# LED_Cube_V6.net
KiCad netlist of a schematic drawn in EAGLE
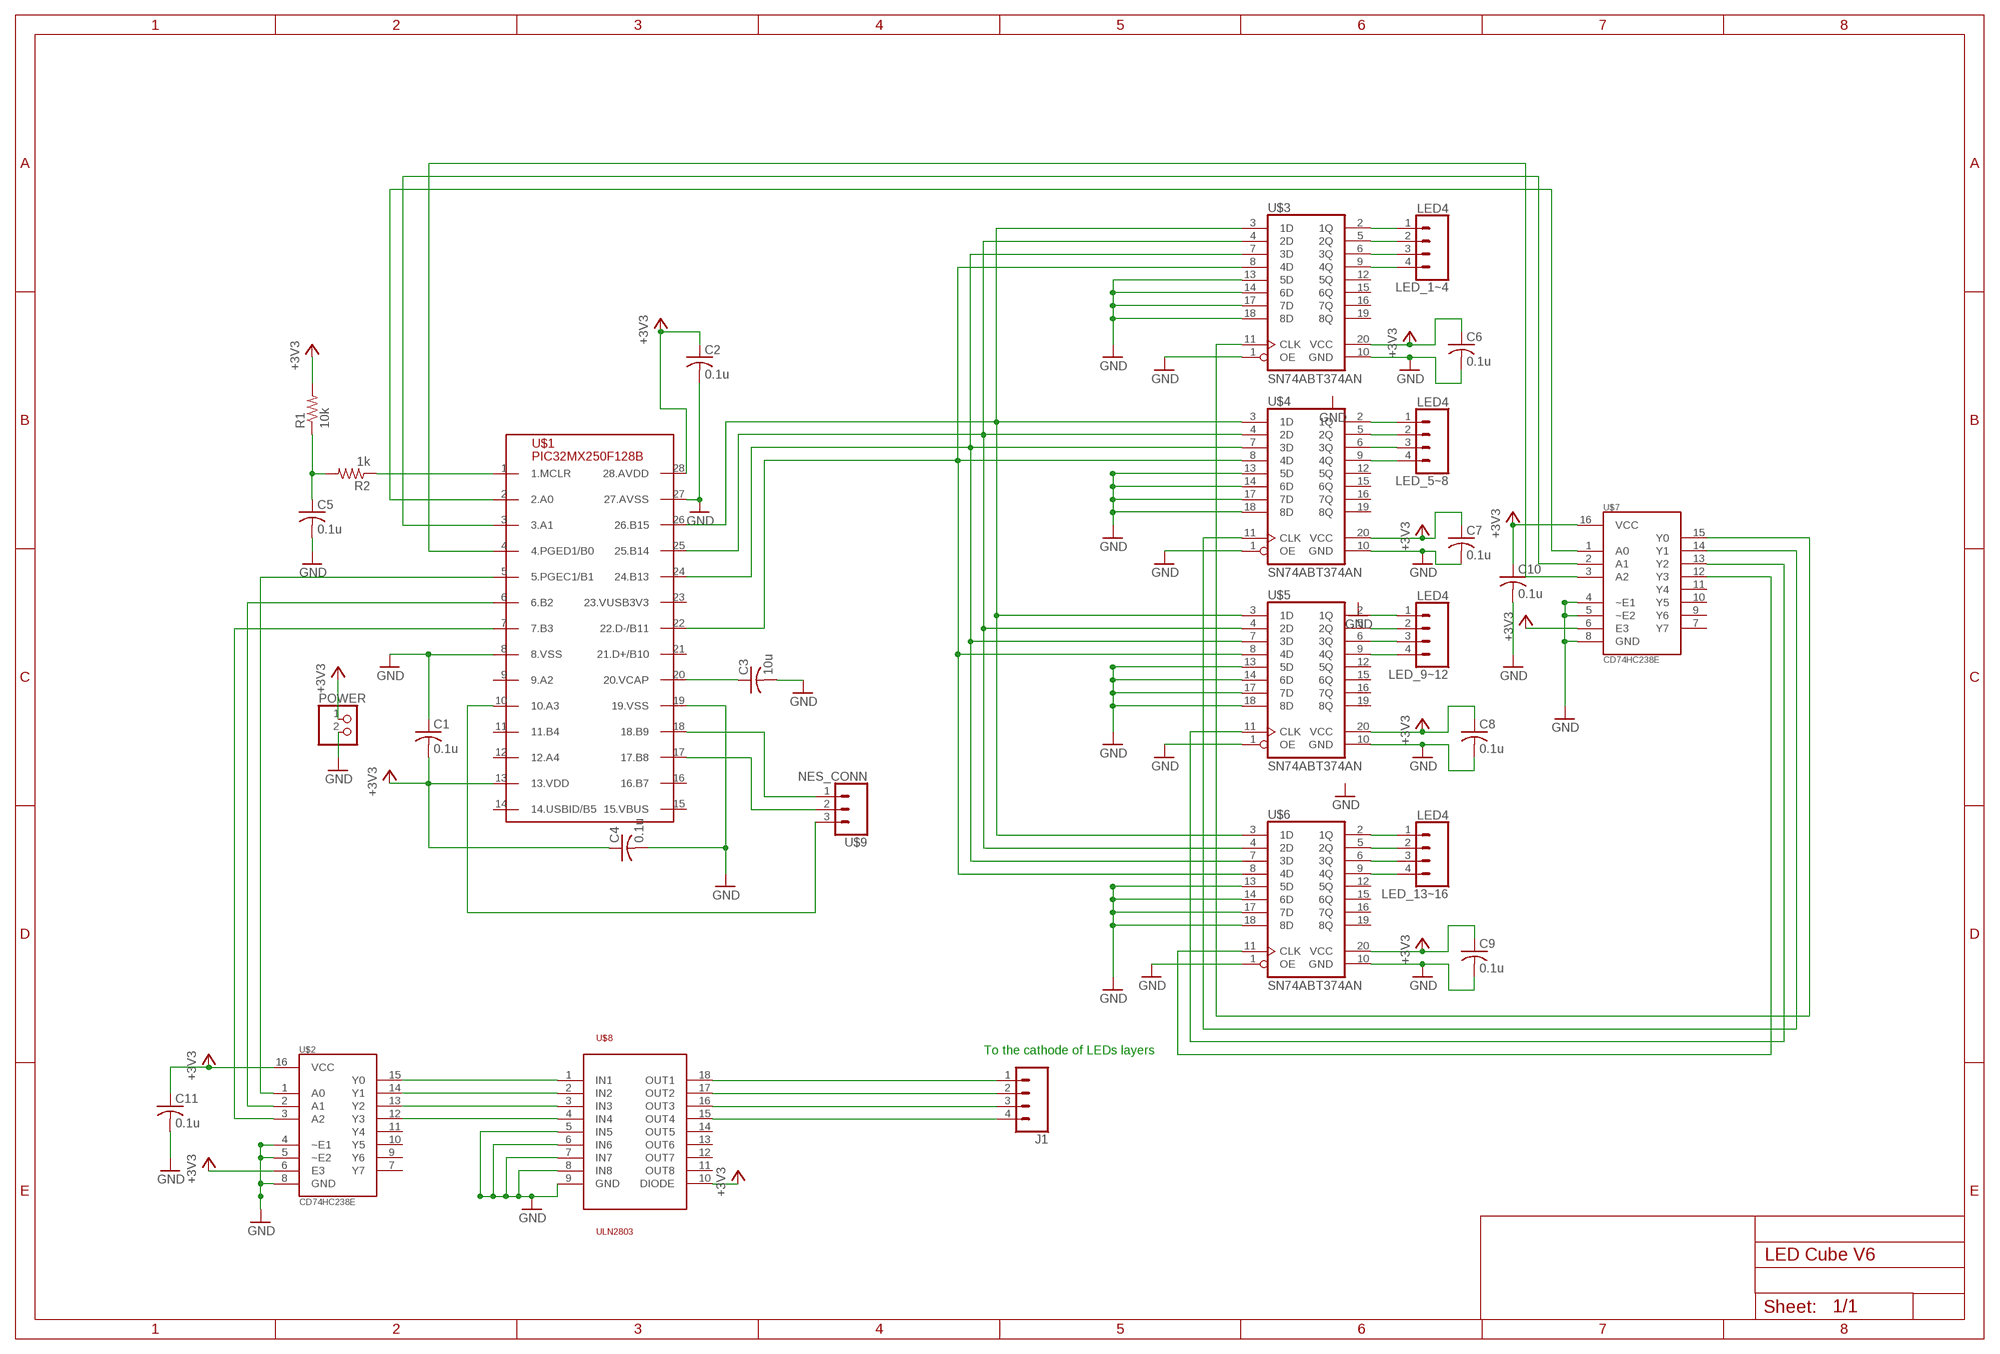
[diagram p0: schematic, sheet 1]

(export (version "E")
  (design (tool "Eeschema 10.0.6"))
  (components
    (comp (ref "C1")
      (value "0.1u")
      (footprint "eagle-import:C025-025X050")
      (libsource (lib "eagle-import") (part "C-US025-025X050"))
    )
    (comp (ref "C2")
      (value "0.1u")
      (footprint "eagle-import:C025-025X050")
      (libsource (lib "eagle-import") (part "C-US025-025X050"))
    )
    (comp (ref "C3")
      (value "10u")
      (footprint "eagle-import:C025-025X050")
      (libsource (lib "eagle-import") (part "C-US025-025X050"))
    )
    (comp (ref "C4")
      (value "0.1u")
      (footprint "eagle-import:C025-025X050")
      (libsource (lib "eagle-import") (part "C-US025-025X050"))
    )
    (comp (ref "C5")
      (value "0.1u")
      (footprint "eagle-import:C025-025X050")
      (libsource (lib "eagle-import") (part "C-US025-025X050"))
    )
    (comp (ref "C6")
      (value "0.1u")
      (footprint "eagle-import:C025-025X050")
      (libsource (lib "eagle-import") (part "C-US025-025X050"))
    )
    (comp (ref "C7")
      (value "0.1u")
      (footprint "eagle-import:C025-025X050")
      (libsource (lib "eagle-import") (part "C-US025-025X050"))
    )
    (comp (ref "C8")
      (value "0.1u")
      (footprint "eagle-import:C025-025X050")
      (libsource (lib "eagle-import") (part "C-US025-025X050"))
    )
    (comp (ref "C9")
      (value "0.1u")
      (footprint "eagle-import:C025-025X050")
      (libsource (lib "eagle-import") (part "C-US025-025X050"))
    )
    (comp (ref "C10")
      (value "0.1u")
      (footprint "eagle-import:C025-025X050")
      (libsource (lib "eagle-import") (part "C-US025-025X050"))
    )
    (comp (ref "C11")
      (value "0.1u")
      (footprint "eagle-import:C025-025X050")
      (libsource (lib "eagle-import") (part "C-US025-025X050"))
    )
    (comp (ref "J1")
      (value "CONN_04")
      (footprint "eagle-import:1X04")
      (libsource (lib "eagle-import") (part "CONN_04"))
    )
    (comp (ref "LED_1~4")
      (value "LED4")
      (footprint "eagle-import:1X04")
      (libsource (lib "eagle-import") (part "LED4"))
    )
    (comp (ref "LED_5~8")
      (value "LED4")
      (footprint "eagle-import:1X04")
      (libsource (lib "eagle-import") (part "LED4"))
    )
    (comp (ref "LED_9~12")
      (value "LED4")
      (footprint "eagle-import:1X04")
      (libsource (lib "eagle-import") (part "LED4"))
    )
    (comp (ref "LED_13~16")
      (value "LED4")
      (footprint "eagle-import:1X04")
      (libsource (lib "eagle-import") (part "LED4"))
    )
    (comp (ref "POWER")
      (value "PINHD-1X2")
      (footprint "eagle-import:1X02")
      (libsource (lib "eagle-import") (part "PINHD-1X2"))
    )
    (comp (ref "R1")
      (value "10k")
      (footprint "eagle-import:0204_7")
      (libsource (lib "eagle-import") (part "R-US_0204/7"))
    )
    (comp (ref "R2")
      (value "1k")
      (footprint "eagle-import:0204_7")
      (libsource (lib "eagle-import") (part "R-US_0204/7"))
    )
    (comp (ref "U$1")
      (value "PIC32MX250F128B")
      (footprint "eagle-import:DIL28-3")
      (libsource (lib "eagle-import") (part "PIC32MX250F128B"))
    )
    (comp (ref "U$2")
      (value "CD74HC238E")
      (footprint "eagle-import:DIL16")
      (libsource (lib "eagle-import") (part "CD74HC238E"))
    )
    (comp (ref "U$3")
      (value "SN74ABT374AN")
      (footprint "eagle-import:DIL20")
      (libsource (lib "eagle-import") (part "SN74ABT374AN"))
    )
    (comp (ref "U$4")
      (value "SN74ABT374AN")
      (footprint "eagle-import:DIL20")
      (libsource (lib "eagle-import") (part "SN74ABT374AN"))
    )
    (comp (ref "U$5")
      (value "SN74ABT374AN")
      (footprint "eagle-import:DIL20")
      (libsource (lib "eagle-import") (part "SN74ABT374AN"))
    )
    (comp (ref "U$6")
      (value "SN74ABT374AN")
      (footprint "eagle-import:DIL20")
      (libsource (lib "eagle-import") (part "SN74ABT374AN"))
    )
    (comp (ref "U$7")
      (value "CD74HC238E")
      (footprint "eagle-import:DIL16")
      (libsource (lib "eagle-import") (part "CD74HC238E"))
    )
    (comp (ref "U$8")
      (value "ULN2803")
      (footprint "eagle-import:SO18L")
      (libsource (lib "eagle-import") (part "ULN2803"))
    )
    (comp (ref "U$9")
      (value "NES_CONN")
      (footprint "eagle-import:1X03")
      (libsource (lib "eagle-import") (part "NES_CONN"))
    )
  )
  (nets
    (net (code "1") (name "+3V3") (class "Default")
      (node (ref "C1") (pin "2") (pinfunction "2_2") (pintype "passive"))
      (node (ref "C10") (pin "1") (pinfunction "1_1") (pintype "passive"))
      (node (ref "C11") (pin "1") (pinfunction "1_1") (pintype "passive"))
      (node (ref "C2") (pin "1") (pinfunction "1_1") (pintype "passive"))
      (node (ref "C4") (pin "1") (pinfunction "1_1") (pintype "passive"))
      (node (ref "C6") (pin "1") (pinfunction "1_1") (pintype "passive"))
      (node (ref "C7") (pin "1") (pinfunction "1_1") (pintype "passive"))
      (node (ref "C8") (pin "1") (pinfunction "1_1") (pintype "passive"))
      (node (ref "C9") (pin "1") (pinfunction "1_1") (pintype "passive"))
      (node (ref "POWER") (pin "1") (pinfunction "1_1") (pintype "passive"))
      (node (ref "R1") (pin "2") (pinfunction "2_2") (pintype "passive"))
      (node (ref "U$1") (pin "13") (pinfunction "13.VDD_13") (pintype "bidirectional"))
      (node (ref "U$1") (pin "28") (pinfunction "28.AVDD_28") (pintype "bidirectional"))
      (node (ref "U$2") (pin "16") (pinfunction "VCC_16") (pintype "bidirectional"))
      (node (ref "U$2") (pin "6") (pinfunction "E3_6") (pintype "bidirectional"))
      (node (ref "U$3") (pin "20") (pinfunction "VCC_20") (pintype "bidirectional"))
      (node (ref "U$4") (pin "20") (pinfunction "VCC_20") (pintype "bidirectional"))
      (node (ref "U$5") (pin "20") (pinfunction "VCC_20") (pintype "bidirectional"))
      (node (ref "U$6") (pin "20") (pinfunction "VCC_20") (pintype "bidirectional"))
      (node (ref "U$7") (pin "16") (pinfunction "VCC_16") (pintype "bidirectional"))
      (node (ref "U$7") (pin "6") (pinfunction "E3_6") (pintype "bidirectional"))
      (node (ref "U$8") (pin "10") (pinfunction "DIODE_10") (pintype "power_in"))
    )
    (net (code "2") (name "GND") (class "Default")
      (node (ref "C1") (pin "1") (pinfunction "1_1") (pintype "passive"))
      (node (ref "C10") (pin "2") (pinfunction "2_2") (pintype "passive"))
      (node (ref "C11") (pin "2") (pinfunction "2_2") (pintype "passive"))
      (node (ref "C2") (pin "2") (pinfunction "2_2") (pintype "passive"))
      (node (ref "C3") (pin "2") (pinfunction "2_2") (pintype "passive"))
      (node (ref "C4") (pin "2") (pinfunction "2_2") (pintype "passive"))
      (node (ref "C5") (pin "2") (pinfunction "2_2") (pintype "passive"))
      (node (ref "C6") (pin "2") (pinfunction "2_2") (pintype "passive"))
      (node (ref "C7") (pin "2") (pinfunction "2_2") (pintype "passive"))
      (node (ref "C8") (pin "2") (pinfunction "2_2") (pintype "passive"))
      (node (ref "C9") (pin "2") (pinfunction "2_2") (pintype "passive"))
      (node (ref "POWER") (pin "2") (pinfunction "2_2") (pintype "passive"))
      (node (ref "U$1") (pin "19") (pinfunction "19.VSS_19") (pintype "bidirectional"))
      (node (ref "U$1") (pin "27") (pinfunction "27.AVSS_27") (pintype "bidirectional"))
      (node (ref "U$1") (pin "8") (pinfunction "8.VSS_8") (pintype "bidirectional"))
      (node (ref "U$2") (pin "4") (pinfunction "~{E1}_4") (pintype "bidirectional"))
      (node (ref "U$2") (pin "5") (pinfunction "~{E2}_5") (pintype "bidirectional"))
      (node (ref "U$2") (pin "8") (pinfunction "GND_8") (pintype "bidirectional"))
      (node (ref "U$3") (pin "1") (pinfunction "OE_1") (pintype "input"))
      (node (ref "U$3") (pin "10") (pinfunction "GND_10") (pintype "bidirectional"))
      (node (ref "U$3") (pin "13") (pinfunction "5D_13") (pintype "input"))
      (node (ref "U$3") (pin "14") (pinfunction "6D_14") (pintype "input"))
      (node (ref "U$3") (pin "17") (pinfunction "7D_17") (pintype "input"))
      (node (ref "U$3") (pin "18") (pinfunction "8D_18") (pintype "input"))
      (node (ref "U$4") (pin "1") (pinfunction "OE_1") (pintype "input"))
      (node (ref "U$4") (pin "10") (pinfunction "GND_10") (pintype "bidirectional"))
      (node (ref "U$4") (pin "13") (pinfunction "5D_13") (pintype "input"))
      (node (ref "U$4") (pin "14") (pinfunction "6D_14") (pintype "input"))
      (node (ref "U$4") (pin "17") (pinfunction "7D_17") (pintype "input"))
      (node (ref "U$4") (pin "18") (pinfunction "8D_18") (pintype "input"))
      (node (ref "U$5") (pin "1") (pinfunction "OE_1") (pintype "input"))
      (node (ref "U$5") (pin "10") (pinfunction "GND_10") (pintype "bidirectional"))
      (node (ref "U$5") (pin "13") (pinfunction "5D_13") (pintype "input"))
      (node (ref "U$5") (pin "14") (pinfunction "6D_14") (pintype "input"))
      (node (ref "U$5") (pin "17") (pinfunction "7D_17") (pintype "input"))
      (node (ref "U$5") (pin "18") (pinfunction "8D_18") (pintype "input"))
      (node (ref "U$6") (pin "1") (pinfunction "OE_1") (pintype "input"))
      (node (ref "U$6") (pin "10") (pinfunction "GND_10") (pintype "bidirectional"))
      (node (ref "U$6") (pin "13") (pinfunction "5D_13") (pintype "input"))
      (node (ref "U$6") (pin "14") (pinfunction "6D_14") (pintype "input"))
      (node (ref "U$6") (pin "17") (pinfunction "7D_17") (pintype "input"))
      (node (ref "U$6") (pin "18") (pinfunction "8D_18") (pintype "input"))
      (node (ref "U$7") (pin "4") (pinfunction "~{E1}_4") (pintype "bidirectional"))
      (node (ref "U$7") (pin "5") (pinfunction "~{E2}_5") (pintype "bidirectional"))
      (node (ref "U$7") (pin "8") (pinfunction "GND_8") (pintype "bidirectional"))
      (node (ref "U$8") (pin "5") (pinfunction "IN5_5") (pintype "input"))
      (node (ref "U$8") (pin "6") (pinfunction "IN6_6") (pintype "input"))
      (node (ref "U$8") (pin "7") (pinfunction "IN7_7") (pintype "input"))
      (node (ref "U$8") (pin "8") (pinfunction "IN8_8") (pintype "input"))
      (node (ref "U$8") (pin "9") (pinfunction "GND_9") (pintype "power_in"))
    )
    (net (code "3") (name "Net-(C5-Pad1)") (class "Default")
      (node (ref "C5") (pin "1") (pinfunction "1_1") (pintype "passive"))
      (node (ref "R1") (pin "1") (pinfunction "1_1") (pintype "passive"))
      (node (ref "R2") (pin "2") (pinfunction "2_2") (pintype "passive"))
    )
    (net (code "4") (name "Net-(U$1-1.MCLR)") (class "Default")
      (node (ref "R2") (pin "1") (pinfunction "1_1") (pintype "passive"))
      (node (ref "U$1") (pin "1") (pinfunction "1.MCLR_1") (pintype "bidirectional"))
    )
    (net (code "5") (name "Net-(U$1-2.A0)") (class "Default")
      (node (ref "U$1") (pin "2") (pinfunction "2.A0_2") (pintype "bidirectional"))
      (node (ref "U$7") (pin "1") (pinfunction "A0_1") (pintype "bidirectional"))
    )
    (net (code "6") (name "Net-(U$1-3.A1)") (class "Default")
      (node (ref "U$1") (pin "3") (pinfunction "3.A1_3") (pintype "bidirectional"))
      (node (ref "U$7") (pin "2") (pinfunction "A1_2") (pintype "bidirectional"))
    )
    (net (code "7") (name "Net-(U$1-4.PGED1{slash}B0)") (class "Default")
      (node (ref "U$1") (pin "4") (pinfunction "4.PGED1/B0_4") (pintype "bidirectional"))
      (node (ref "U$7") (pin "3") (pinfunction "A2_3") (pintype "bidirectional"))
    )
    (net (code "8") (name "Net-(U$1-5.PGEC1{slash}B1)") (class "Default")
      (node (ref "U$1") (pin "5") (pinfunction "5.PGEC1/B1_5") (pintype "bidirectional"))
      (node (ref "U$2") (pin "1") (pinfunction "A0_1") (pintype "bidirectional"))
    )
    (net (code "9") (name "Net-(U$1-6.B2)") (class "Default")
      (node (ref "U$1") (pin "6") (pinfunction "6.B2_6") (pintype "bidirectional"))
      (node (ref "U$2") (pin "2") (pinfunction "A1_2") (pintype "bidirectional"))
    )
    (net (code "10") (name "Net-(U$1-7.B3)") (class "Default")
      (node (ref "U$1") (pin "7") (pinfunction "7.B3_7") (pintype "bidirectional"))
      (node (ref "U$2") (pin "3") (pinfunction "A2_3") (pintype "bidirectional"))
    )
    (net (code "11") (name "Net-(U$1-10.A3)") (class "Default")
      (node (ref "U$1") (pin "10") (pinfunction "10.A3_10") (pintype "bidirectional"))
      (node (ref "U$9") (pin "3") (pinfunction "3_3") (pintype "passive"))
    )
    (net (code "12") (name "Net-(U$1-17.B8)") (class "Default")
      (node (ref "U$1") (pin "17") (pinfunction "17.B8_17") (pintype "bidirectional"))
      (node (ref "U$9") (pin "2") (pinfunction "2_2") (pintype "passive"))
    )
    (net (code "13") (name "Net-(U$1-18.B9)") (class "Default")
      (node (ref "U$1") (pin "18") (pinfunction "18.B9_18") (pintype "bidirectional"))
      (node (ref "U$9") (pin "1") (pinfunction "1_1") (pintype "passive"))
    )
    (net (code "14") (name "Net-(U$1-20.VCAP)") (class "Default")
      (node (ref "C3") (pin "1") (pinfunction "1_1") (pintype "passive"))
      (node (ref "U$1") (pin "20") (pinfunction "20.VCAP_20") (pintype "bidirectional"))
    )
    (net (code "15") (name "Net-(U$1-22.D-{slash}B11)") (class "Default")
      (node (ref "U$1") (pin "22") (pinfunction "22.D-/B11_22") (pintype "bidirectional"))
      (node (ref "U$3") (pin "8") (pinfunction "4D_8") (pintype "input"))
      (node (ref "U$4") (pin "8") (pinfunction "4D_8") (pintype "input"))
      (node (ref "U$5") (pin "8") (pinfunction "4D_8") (pintype "input"))
      (node (ref "U$6") (pin "8") (pinfunction "4D_8") (pintype "input"))
    )
    (net (code "16") (name "Net-(U$1-24.B13)") (class "Default")
      (node (ref "U$1") (pin "24") (pinfunction "24.B13_24") (pintype "bidirectional"))
      (node (ref "U$3") (pin "7") (pinfunction "3D_7") (pintype "input"))
      (node (ref "U$4") (pin "7") (pinfunction "3D_7") (pintype "input"))
      (node (ref "U$5") (pin "7") (pinfunction "3D_7") (pintype "input"))
      (node (ref "U$6") (pin "7") (pinfunction "3D_7") (pintype "input"))
    )
    (net (code "17") (name "Net-(U$1-25.B14)") (class "Default")
      (node (ref "U$1") (pin "25") (pinfunction "25.B14_25") (pintype "bidirectional"))
      (node (ref "U$3") (pin "4") (pinfunction "2D_4") (pintype "input"))
      (node (ref "U$4") (pin "4") (pinfunction "2D_4") (pintype "input"))
      (node (ref "U$5") (pin "4") (pinfunction "2D_4") (pintype "input"))
      (node (ref "U$6") (pin "4") (pinfunction "2D_4") (pintype "input"))
    )
    (net (code "18") (name "Net-(U$1-26.B15)") (class "Default")
      (node (ref "U$1") (pin "26") (pinfunction "26.B15_26") (pintype "bidirectional"))
      (node (ref "U$3") (pin "3") (pinfunction "1D_3") (pintype "input"))
      (node (ref "U$4") (pin "3") (pinfunction "1D_3") (pintype "input"))
      (node (ref "U$5") (pin "3") (pinfunction "1D_3") (pintype "input"))
      (node (ref "U$6") (pin "3") (pinfunction "1D_3") (pintype "input"))
    )
    (net (code "19") (name "Net-(U$2-Y0)") (class "Default")
      (node (ref "U$2") (pin "15") (pinfunction "Y0_15") (pintype "bidirectional"))
      (node (ref "U$8") (pin "1") (pinfunction "IN1_1") (pintype "input"))
    )
    (net (code "20") (name "Net-(U$2-Y1)") (class "Default")
      (node (ref "U$2") (pin "14") (pinfunction "Y1_14") (pintype "bidirectional"))
      (node (ref "U$8") (pin "2") (pinfunction "IN2_2") (pintype "input"))
    )
    (net (code "21") (name "Net-(U$2-Y2)") (class "Default")
      (node (ref "U$2") (pin "13") (pinfunction "Y2_13") (pintype "bidirectional"))
      (node (ref "U$8") (pin "3") (pinfunction "IN3_3") (pintype "input"))
    )
    (net (code "22") (name "Net-(U$2-Y3)") (class "Default")
      (node (ref "U$2") (pin "12") (pinfunction "Y3_12") (pintype "bidirectional"))
      (node (ref "U$8") (pin "4") (pinfunction "IN4_4") (pintype "input"))
    )
    (net (code "23") (name "Net-(U$3-1Q)") (class "Default")
      (node (ref "LED_1~4") (pin "1") (pinfunction "1_1") (pintype "passive"))
      (node (ref "U$3") (pin "2") (pinfunction "1Q_2") (pintype "tri_state"))
    )
    (net (code "24") (name "Net-(U$3-2Q)") (class "Default")
      (node (ref "LED_1~4") (pin "2") (pinfunction "2_2") (pintype "passive"))
      (node (ref "U$3") (pin "5") (pinfunction "2Q_5") (pintype "tri_state"))
    )
    (net (code "25") (name "Net-(U$3-3Q)") (class "Default")
      (node (ref "LED_1~4") (pin "3") (pinfunction "3_3") (pintype "passive"))
      (node (ref "U$3") (pin "6") (pinfunction "3Q_6") (pintype "tri_state"))
    )
    (net (code "26") (name "Net-(U$3-4Q)") (class "Default")
      (node (ref "LED_1~4") (pin "4") (pinfunction "4_4") (pintype "passive"))
      (node (ref "U$3") (pin "9") (pinfunction "4Q_9") (pintype "tri_state"))
    )
    (net (code "27") (name "Net-(U$3-CLK)") (class "Default")
      (node (ref "U$3") (pin "11") (pinfunction "CLK_11") (pintype "input"))
      (node (ref "U$7") (pin "15") (pinfunction "Y0_15") (pintype "bidirectional"))
    )
    (net (code "28") (name "Net-(U$4-1Q)") (class "Default")
      (node (ref "LED_5~8") (pin "1") (pinfunction "1_1") (pintype "passive"))
      (node (ref "U$4") (pin "2") (pinfunction "1Q_2") (pintype "tri_state"))
    )
    (net (code "29") (name "Net-(U$4-2Q)") (class "Default")
      (node (ref "LED_5~8") (pin "2") (pinfunction "2_2") (pintype "passive"))
      (node (ref "U$4") (pin "5") (pinfunction "2Q_5") (pintype "tri_state"))
    )
    (net (code "30") (name "Net-(U$4-3Q)") (class "Default")
      (node (ref "LED_5~8") (pin "3") (pinfunction "3_3") (pintype "passive"))
      (node (ref "U$4") (pin "6") (pinfunction "3Q_6") (pintype "tri_state"))
    )
    (net (code "31") (name "Net-(U$4-4Q)") (class "Default")
      (node (ref "LED_5~8") (pin "4") (pinfunction "4_4") (pintype "passive"))
      (node (ref "U$4") (pin "9") (pinfunction "4Q_9") (pintype "tri_state"))
    )
    (net (code "32") (name "Net-(U$4-CLK)") (class "Default")
      (node (ref "U$4") (pin "11") (pinfunction "CLK_11") (pintype "input"))
      (node (ref "U$7") (pin "14") (pinfunction "Y1_14") (pintype "bidirectional"))
    )
    (net (code "33") (name "Net-(U$5-1Q)") (class "Default")
      (node (ref "LED_9~12") (pin "1") (pinfunction "1_1") (pintype "passive"))
      (node (ref "U$5") (pin "2") (pinfunction "1Q_2") (pintype "tri_state"))
    )
    (net (code "34") (name "Net-(U$5-2Q)") (class "Default")
      (node (ref "LED_9~12") (pin "2") (pinfunction "2_2") (pintype "passive"))
      (node (ref "U$5") (pin "5") (pinfunction "2Q_5") (pintype "tri_state"))
    )
    (net (code "35") (name "Net-(U$5-3Q)") (class "Default")
      (node (ref "LED_9~12") (pin "3") (pinfunction "3_3") (pintype "passive"))
      (node (ref "U$5") (pin "6") (pinfunction "3Q_6") (pintype "tri_state"))
    )
    (net (code "36") (name "Net-(U$5-4Q)") (class "Default")
      (node (ref "LED_9~12") (pin "4") (pinfunction "4_4") (pintype "passive"))
      (node (ref "U$5") (pin "9") (pinfunction "4Q_9") (pintype "tri_state"))
    )
    (net (code "37") (name "Net-(U$5-CLK)") (class "Default")
      (node (ref "U$5") (pin "11") (pinfunction "CLK_11") (pintype "input"))
      (node (ref "U$7") (pin "13") (pinfunction "Y2_13") (pintype "bidirectional"))
    )
    (net (code "38") (name "Net-(U$6-1Q)") (class "Default")
      (node (ref "LED_13~16") (pin "1") (pinfunction "1_1") (pintype "passive"))
      (node (ref "U$6") (pin "2") (pinfunction "1Q_2") (pintype "tri_state"))
    )
    (net (code "39") (name "Net-(U$6-2Q)") (class "Default")
      (node (ref "LED_13~16") (pin "2") (pinfunction "2_2") (pintype "passive"))
      (node (ref "U$6") (pin "5") (pinfunction "2Q_5") (pintype "tri_state"))
    )
    (net (code "40") (name "Net-(U$6-3Q)") (class "Default")
      (node (ref "LED_13~16") (pin "3") (pinfunction "3_3") (pintype "passive"))
      (node (ref "U$6") (pin "6") (pinfunction "3Q_6") (pintype "tri_state"))
    )
    (net (code "41") (name "Net-(U$6-4Q)") (class "Default")
      (node (ref "LED_13~16") (pin "4") (pinfunction "4_4") (pintype "passive"))
      (node (ref "U$6") (pin "9") (pinfunction "4Q_9") (pintype "tri_state"))
    )
    (net (code "42") (name "Net-(U$6-CLK)") (class "Default")
      (node (ref "U$6") (pin "11") (pinfunction "CLK_11") (pintype "input"))
      (node (ref "U$7") (pin "12") (pinfunction "Y3_12") (pintype "bidirectional"))
    )
    (net (code "43") (name "Net-(U$8-OUT1)") (class "Default")
      (node (ref "J1") (pin "1") (pinfunction "1_1") (pintype "passive"))
      (node (ref "U$8") (pin "18") (pinfunction "OUT1_18") (pintype "open_collector"))
    )
    (net (code "44") (name "Net-(U$8-OUT2)") (class "Default")
      (node (ref "J1") (pin "2") (pinfunction "2_2") (pintype "passive"))
      (node (ref "U$8") (pin "17") (pinfunction "OUT2_17") (pintype "open_collector"))
    )
    (net (code "45") (name "Net-(U$8-OUT3)") (class "Default")
      (node (ref "J1") (pin "3") (pinfunction "3_3") (pintype "passive"))
      (node (ref "U$8") (pin "16") (pinfunction "OUT3_16") (pintype "open_collector"))
    )
    (net (code "46") (name "Net-(U$8-OUT4)") (class "Default")
      (node (ref "J1") (pin "4") (pinfunction "4_4") (pintype "passive"))
      (node (ref "U$8") (pin "15") (pinfunction "OUT4_15") (pintype "open_collector"))
    )
    (net (code "47") (name "unconnected-(U$1-9.A2-Pad9)") (class "Default")
      (node (ref "U$1") (pin "9") (pinfunction "9.A2_9") (pintype "bidirectional"))
    )
    (net (code "48") (name "unconnected-(U$1-11.B4-Pad11)") (class "Default")
      (node (ref "U$1") (pin "11") (pinfunction "11.B4_11") (pintype "bidirectional"))
    )
    (net (code "49") (name "unconnected-(U$1-12.A4-Pad12)") (class "Default")
      (node (ref "U$1") (pin "12") (pinfunction "12.A4_12") (pintype "bidirectional"))
    )
    (net (code "50") (name "unconnected-(U$1-14.USBID{slash}B5-Pad14)") (class "Default")
      (node (ref "U$1") (pin "14") (pinfunction "14.USBID/B5_14") (pintype "bidirectional"))
    )
    (net (code "51") (name "unconnected-(U$1-15.VBUS-Pad15)") (class "Default")
      (node (ref "U$1") (pin "15") (pinfunction "15.VBUS_15") (pintype "bidirectional"))
    )
    (net (code "52") (name "unconnected-(U$1-16.B7-Pad16)") (class "Default")
      (node (ref "U$1") (pin "16") (pinfunction "16.B7_16") (pintype "bidirectional"))
    )
    (net (code "53") (name "unconnected-(U$1-21.D+{slash}B10-Pad21)") (class "Default")
      (node (ref "U$1") (pin "21") (pinfunction "21.D+/B10_21") (pintype "bidirectional"))
    )
    (net (code "54") (name "unconnected-(U$1-23.VUSB3V3-Pad23)") (class "Default")
      (node (ref "U$1") (pin "23") (pinfunction "23.VUSB3V3_23") (pintype "bidirectional"))
    )
    (net (code "55") (name "unconnected-(U$2-Y4-Pad11)") (class "Default")
      (node (ref "U$2") (pin "11") (pinfunction "Y4_11") (pintype "bidirectional"))
    )
    (net (code "56") (name "unconnected-(U$2-Y5-Pad10)") (class "Default")
      (node (ref "U$2") (pin "10") (pinfunction "Y5_10") (pintype "bidirectional"))
    )
    (net (code "57") (name "unconnected-(U$2-Y6-Pad9)") (class "Default")
      (node (ref "U$2") (pin "9") (pinfunction "Y6_9") (pintype "bidirectional"))
    )
    (net (code "58") (name "unconnected-(U$2-Y7-Pad7)") (class "Default")
      (node (ref "U$2") (pin "7") (pinfunction "Y7_7") (pintype "bidirectional"))
    )
    (net (code "59") (name "unconnected-(U$3-5Q-Pad12)") (class "Default")
      (node (ref "U$3") (pin "12") (pinfunction "5Q_12") (pintype "tri_state"))
    )
    (net (code "60") (name "unconnected-(U$3-6Q-Pad15)") (class "Default")
      (node (ref "U$3") (pin "15") (pinfunction "6Q_15") (pintype "tri_state"))
    )
    (net (code "61") (name "unconnected-(U$3-7Q-Pad16)") (class "Default")
      (node (ref "U$3") (pin "16") (pinfunction "7Q_16") (pintype "tri_state"))
    )
    (net (code "62") (name "unconnected-(U$3-8Q-Pad19)") (class "Default")
      (node (ref "U$3") (pin "19") (pinfunction "8Q_19") (pintype "tri_state"))
    )
    (net (code "63") (name "unconnected-(U$4-5Q-Pad12)") (class "Default")
      (node (ref "U$4") (pin "12") (pinfunction "5Q_12") (pintype "tri_state"))
    )
    (net (code "64") (name "unconnected-(U$4-6Q-Pad15)") (class "Default")
      (node (ref "U$4") (pin "15") (pinfunction "6Q_15") (pintype "tri_state"))
    )
    (net (code "65") (name "unconnected-(U$4-7Q-Pad16)") (class "Default")
      (node (ref "U$4") (pin "16") (pinfunction "7Q_16") (pintype "tri_state"))
    )
    (net (code "66") (name "unconnected-(U$4-8Q-Pad19)") (class "Default")
      (node (ref "U$4") (pin "19") (pinfunction "8Q_19") (pintype "tri_state"))
    )
    (net (code "67") (name "unconnected-(U$5-5Q-Pad12)") (class "Default")
      (node (ref "U$5") (pin "12") (pinfunction "5Q_12") (pintype "tri_state"))
    )
    (net (code "68") (name "unconnected-(U$5-6Q-Pad15)") (class "Default")
      (node (ref "U$5") (pin "15") (pinfunction "6Q_15") (pintype "tri_state"))
    )
    (net (code "69") (name "unconnected-(U$5-7Q-Pad16)") (class "Default")
      (node (ref "U$5") (pin "16") (pinfunction "7Q_16") (pintype "tri_state"))
    )
    (net (code "70") (name "unconnected-(U$5-8Q-Pad19)") (class "Default")
      (node (ref "U$5") (pin "19") (pinfunction "8Q_19") (pintype "tri_state"))
    )
    (net (code "71") (name "unconnected-(U$6-5Q-Pad12)") (class "Default")
      (node (ref "U$6") (pin "12") (pinfunction "5Q_12") (pintype "tri_state"))
    )
    (net (code "72") (name "unconnected-(U$6-6Q-Pad15)") (class "Default")
      (node (ref "U$6") (pin "15") (pinfunction "6Q_15") (pintype "tri_state"))
    )
    (net (code "73") (name "unconnected-(U$6-7Q-Pad16)") (class "Default")
      (node (ref "U$6") (pin "16") (pinfunction "7Q_16") (pintype "tri_state"))
    )
    (net (code "74") (name "unconnected-(U$6-8Q-Pad19)") (class "Default")
      (node (ref "U$6") (pin "19") (pinfunction "8Q_19") (pintype "tri_state"))
    )
    (net (code "75") (name "unconnected-(U$7-Y4-Pad11)") (class "Default")
      (node (ref "U$7") (pin "11") (pinfunction "Y4_11") (pintype "bidirectional"))
    )
    (net (code "76") (name "unconnected-(U$7-Y5-Pad10)") (class "Default")
      (node (ref "U$7") (pin "10") (pinfunction "Y5_10") (pintype "bidirectional"))
    )
    (net (code "77") (name "unconnected-(U$7-Y6-Pad9)") (class "Default")
      (node (ref "U$7") (pin "9") (pinfunction "Y6_9") (pintype "bidirectional"))
    )
    (net (code "78") (name "unconnected-(U$7-Y7-Pad7)") (class "Default")
      (node (ref "U$7") (pin "7") (pinfunction "Y7_7") (pintype "bidirectional"))
    )
    (net (code "79") (name "unconnected-(U$8-OUT5-Pad14)") (class "Default")
      (node (ref "U$8") (pin "14") (pinfunction "OUT5_14") (pintype "open_collector"))
    )
    (net (code "80") (name "unconnected-(U$8-OUT6-Pad13)") (class "Default")
      (node (ref "U$8") (pin "13") (pinfunction "OUT6_13") (pintype "open_collector"))
    )
    (net (code "81") (name "unconnected-(U$8-OUT7-Pad12)") (class "Default")
      (node (ref "U$8") (pin "12") (pinfunction "OUT7_12") (pintype "open_collector"))
    )
    (net (code "82") (name "unconnected-(U$8-OUT8-Pad11)") (class "Default")
      (node (ref "U$8") (pin "11") (pinfunction "OUT8_11") (pintype "open_collector"))
    )
  )
)
